# grids_v02.net
KiCad netlist of a schematic drawn in EAGLE
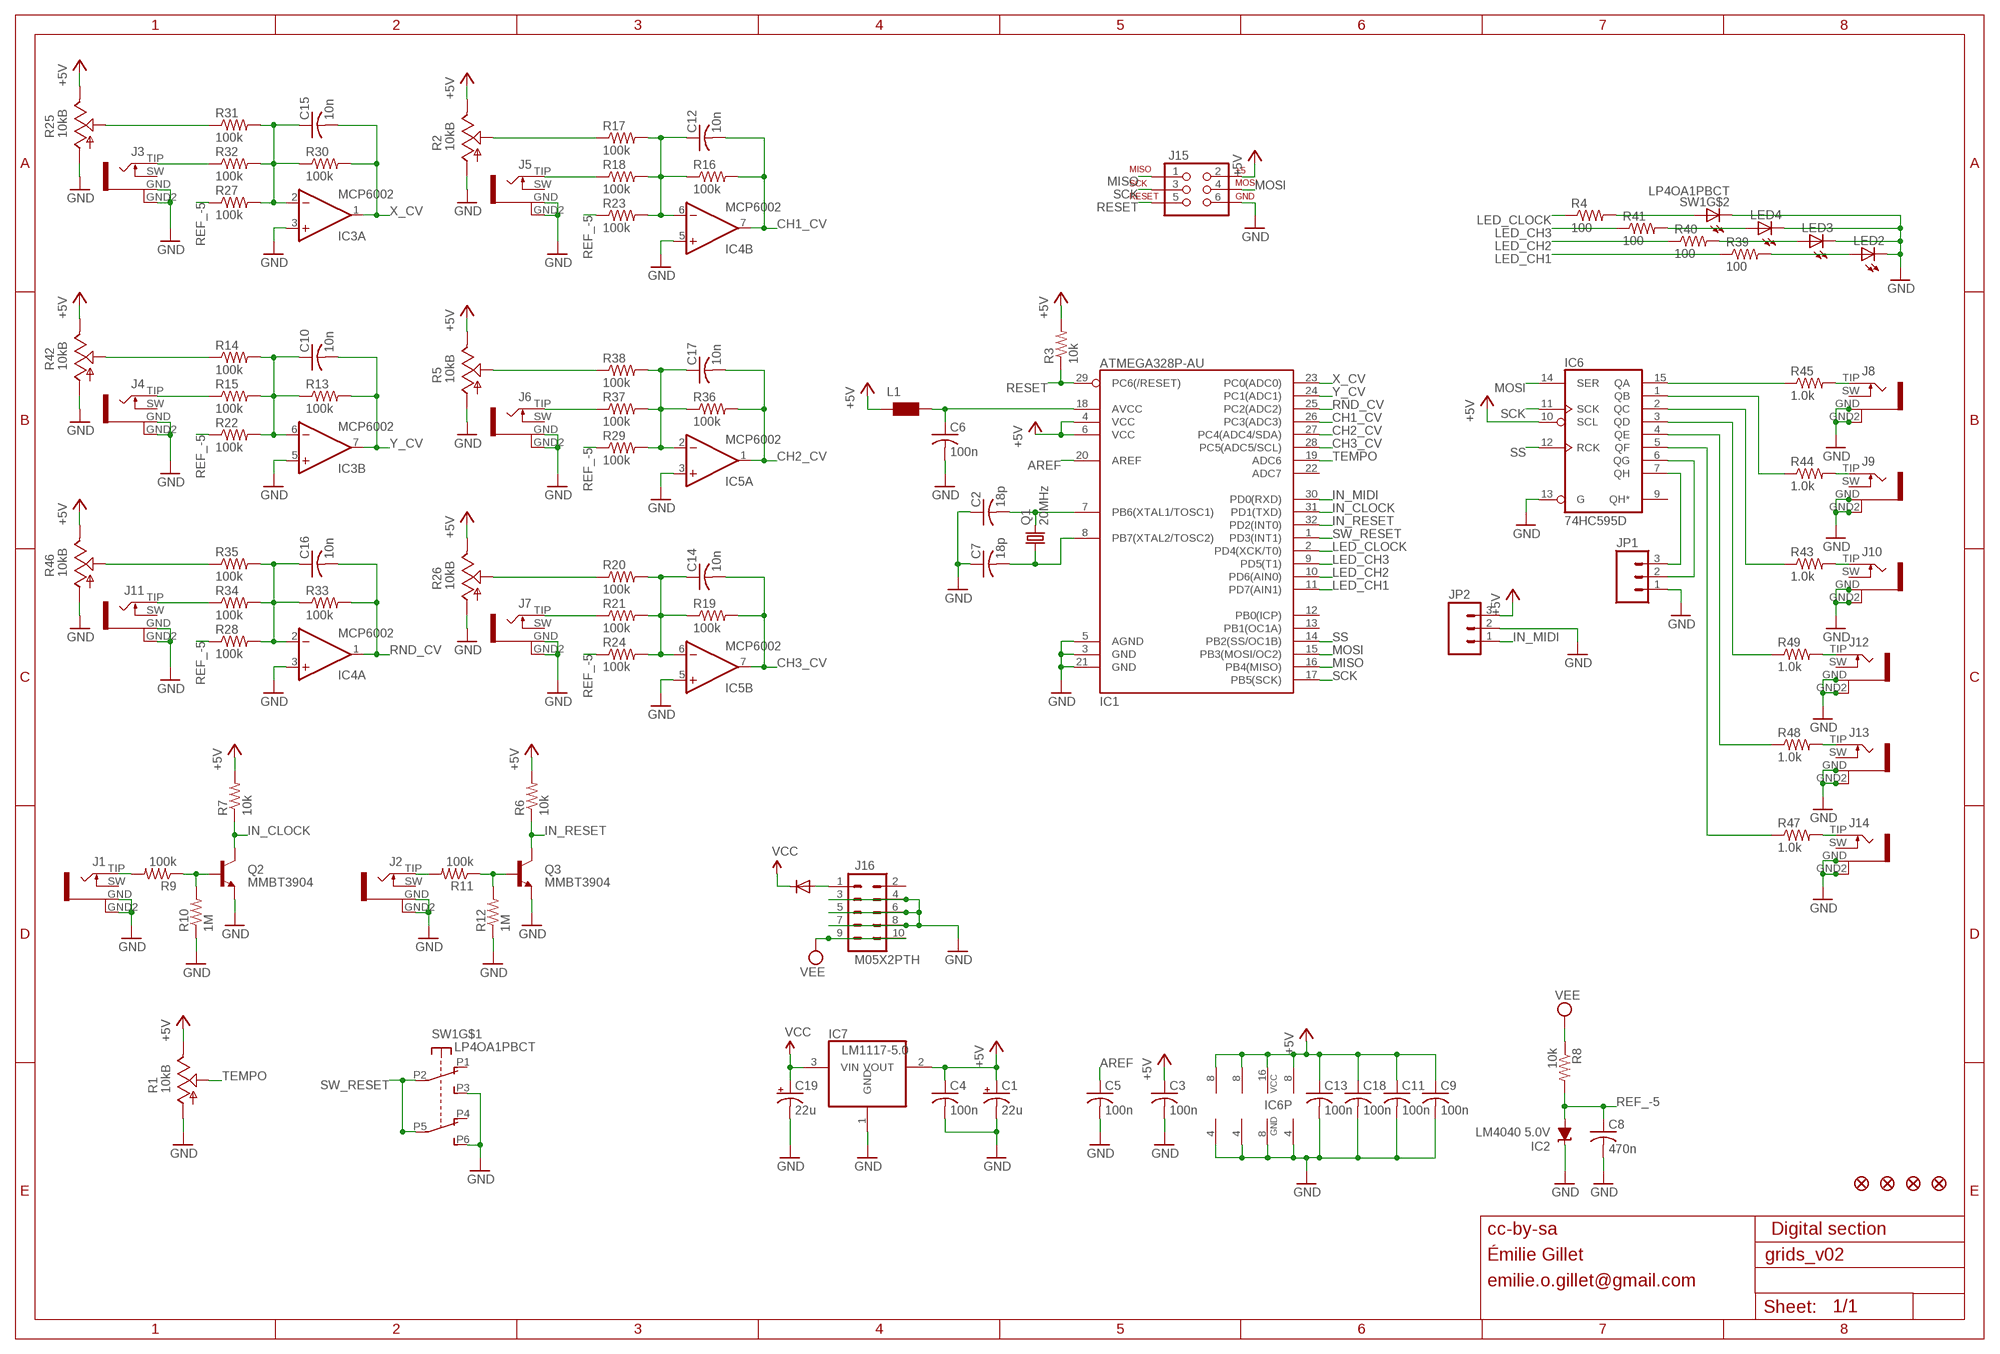
[diagram p0: schematic, sheet 1]

(export (version "E")
  (design (tool "Eeschema 10.0.6"))
  (components
    (comp (ref "C1")
      (value "22u")
      (footprint "eagle-import:PANASONIC_C")
      (libsource (lib "eagle-import") (part "CPOL-USC"))
    )
    (comp (ref "C2")
      (value "18p")
      (footprint "eagle-import:C0603")
      (libsource (lib "eagle-import") (part "C-USC0603"))
    )
    (comp (ref "C3")
      (value "100n")
      (footprint "eagle-import:C0603")
      (libsource (lib "eagle-import") (part "C-USC0603"))
    )
    (comp (ref "C4")
      (value "100n")
      (footprint "eagle-import:C0603")
      (libsource (lib "eagle-import") (part "C-USC0603"))
    )
    (comp (ref "C5")
      (value "100n")
      (footprint "eagle-import:C0603")
      (libsource (lib "eagle-import") (part "C-USC0603"))
    )
    (comp (ref "C6")
      (value "100n")
      (footprint "eagle-import:C0603")
      (libsource (lib "eagle-import") (part "C-USC0603"))
    )
    (comp (ref "C7")
      (value "18p")
      (footprint "eagle-import:C0603")
      (libsource (lib "eagle-import") (part "C-USC0603"))
    )
    (comp (ref "C8")
      (value "470n")
      (footprint "eagle-import:C0603")
      (libsource (lib "eagle-import") (part "C-USC0603"))
    )
    (comp (ref "C9")
      (value "100n")
      (footprint "eagle-import:C0603")
      (libsource (lib "eagle-import") (part "C-USC0603"))
    )
    (comp (ref "C10")
      (value "10n")
      (footprint "eagle-import:C0603")
      (libsource (lib "eagle-import") (part "C-USC0603"))
    )
    (comp (ref "C11")
      (value "100n")
      (footprint "eagle-import:C0603")
      (libsource (lib "eagle-import") (part "C-USC0603"))
    )
    (comp (ref "C12")
      (value "10n")
      (footprint "eagle-import:C0603")
      (libsource (lib "eagle-import") (part "C-USC0603"))
    )
    (comp (ref "C13")
      (value "100n")
      (footprint "eagle-import:C0603")
      (libsource (lib "eagle-import") (part "C-USC0603"))
    )
    (comp (ref "C14")
      (value "10n")
      (footprint "eagle-import:C0603")
      (libsource (lib "eagle-import") (part "C-USC0603"))
    )
    (comp (ref "C15")
      (value "10n")
      (footprint "eagle-import:C0603")
      (libsource (lib "eagle-import") (part "C-USC0603"))
    )
    (comp (ref "C16")
      (value "10n")
      (footprint "eagle-import:C0603")
      (libsource (lib "eagle-import") (part "C-USC0603"))
    )
    (comp (ref "C17")
      (value "10n")
      (footprint "eagle-import:C0603")
      (libsource (lib "eagle-import") (part "C-USC0603"))
    )
    (comp (ref "C18")
      (value "100n")
      (footprint "eagle-import:C0603")
      (libsource (lib "eagle-import") (part "C-USC0603"))
    )
    (comp (ref "C19")
      (value "22u")
      (footprint "eagle-import:PANASONIC_C")
      (libsource (lib "eagle-import") (part "CPOL-USC"))
    )
    (comp (ref "D1")
      (value "1N5819HW")
      (footprint "eagle-import:SOD123")
      (libsource (lib "eagle-import") (part "DIODE-SOD123"))
    )
    (comp (ref "F1")
      (value "FIDUCIAL1X2")
      (footprint "eagle-import:FIDUCIAL-1X2")
      (libsource (lib "eagle-import") (part "FIDUCIAL1X2"))
    )
    (comp (ref "F2")
      (value "FIDUCIAL1X2")
      (footprint "eagle-import:FIDUCIAL-1X2")
      (libsource (lib "eagle-import") (part "FIDUCIAL1X2"))
    )
    (comp (ref "F3")
      (value "FIDUCIAL1X2")
      (footprint "eagle-import:FIDUCIAL-1X2")
      (libsource (lib "eagle-import") (part "FIDUCIAL1X2"))
    )
    (comp (ref "F4")
      (value "FIDUCIAL1X2")
      (footprint "eagle-import:FIDUCIAL-1X2")
      (libsource (lib "eagle-import") (part "FIDUCIAL1X2"))
    )
    (comp (ref "IC1")
      (value "ATMEGA328P-AU")
      (footprint "eagle-import:TQFP32-08")
      (libsource (lib "eagle-import") (part "ATMEGA168"))
    )
    (comp (ref "IC2")
      (value "LM4040 5.0V")
      (footprint "eagle-import:DBZ_R-PDSO-G3")
      (libsource (lib "eagle-import") (part "LM4041DBZC12"))
    )
    (comp (ref "IC3")
      (value "MCP6002")
      (footprint "eagle-import:SO08")
      (libsource (lib "eagle-import") (part "TL072D"))
    )
    (comp (ref "IC4")
      (value "MCP6002")
      (footprint "eagle-import:SO08")
      (libsource (lib "eagle-import") (part "TL072D"))
    )
    (comp (ref "IC5")
      (value "MCP6002")
      (footprint "eagle-import:SO08")
      (libsource (lib "eagle-import") (part "TL072D"))
    )
    (comp (ref "IC6")
      (value "74HC595D")
      (footprint "eagle-import:SO16")
      (libsource (lib "eagle-import") (part "74595DHC"))
    )
    (comp (ref "IC7")
      (value "LM1117-5.0")
      (footprint "eagle-import:SOT223")
      (libsource (lib "eagle-import") (part "REG1117"))
    )
    (comp (ref "J1")
      (value "PJ301WQP")
      (footprint "eagle-import:WQP_PJ_301BM")
      (libsource (lib "eagle-import") (part "PJ301WQP"))
    )
    (comp (ref "J2")
      (value "PJ301WQP")
      (footprint "eagle-import:WQP_PJ_301BM")
      (libsource (lib "eagle-import") (part "PJ301WQP"))
    )
    (comp (ref "J3")
      (value "PJ301WQP")
      (footprint "eagle-import:WQP_PJ_301BM")
      (libsource (lib "eagle-import") (part "PJ301WQP"))
    )
    (comp (ref "J4")
      (value "PJ301WQP")
      (footprint "eagle-import:WQP_PJ_301BM")
      (libsource (lib "eagle-import") (part "PJ301WQP"))
    )
    (comp (ref "J5")
      (value "PJ301WQP")
      (footprint "eagle-import:WQP_PJ_301BM")
      (libsource (lib "eagle-import") (part "PJ301WQP"))
    )
    (comp (ref "J6")
      (value "PJ301WQP")
      (footprint "eagle-import:WQP_PJ_301BM")
      (libsource (lib "eagle-import") (part "PJ301WQP"))
    )
    (comp (ref "J7")
      (value "PJ301WQP")
      (footprint "eagle-import:WQP_PJ_301BM")
      (libsource (lib "eagle-import") (part "PJ301WQP"))
    )
    (comp (ref "J8")
      (value "PJ301WQP")
      (footprint "eagle-import:WQP_PJ_301BM")
      (libsource (lib "eagle-import") (part "PJ301WQP"))
    )
    (comp (ref "J9")
      (value "PJ301WQP")
      (footprint "eagle-import:WQP_PJ_301BM")
      (libsource (lib "eagle-import") (part "PJ301WQP"))
    )
    (comp (ref "J10")
      (value "PJ301WQP")
      (footprint "eagle-import:WQP_PJ_301BM")
      (libsource (lib "eagle-import") (part "PJ301WQP"))
    )
    (comp (ref "J11")
      (value "PJ301WQP")
      (footprint "eagle-import:WQP_PJ_301BM")
      (libsource (lib "eagle-import") (part "PJ301WQP"))
    )
    (comp (ref "J12")
      (value "PJ301WQP")
      (footprint "eagle-import:WQP_PJ_301BM")
      (libsource (lib "eagle-import") (part "PJ301WQP"))
    )
    (comp (ref "J13")
      (value "PJ301WQP")
      (footprint "eagle-import:WQP_PJ_301BM")
      (libsource (lib "eagle-import") (part "PJ301WQP"))
    )
    (comp (ref "J14")
      (value "PJ301WQP")
      (footprint "eagle-import:WQP_PJ_301BM")
      (libsource (lib "eagle-import") (part "PJ301WQP"))
    )
    (comp (ref "J15")
      (value "AVR_SPI_PRG_6PTH")
      (footprint "eagle-import:2X3")
      (libsource (lib "eagle-import") (part "AVR_SPI_PRG_6PTH"))
    )
    (comp (ref "J16")
      (value "M05X2PTH")
      (footprint "eagle-import:AVR_ICSP")
      (libsource (lib "eagle-import") (part "M05X2PTH"))
    )
    (comp (ref "JP1")
      (value "M03PTH")
      (footprint "eagle-import:1X03")
      (libsource (lib "eagle-import") (part "M03PTH"))
    )
    (comp (ref "JP2")
      (value "M03PTH")
      (footprint "eagle-import:1X03")
      (libsource (lib "eagle-import") (part "M03PTH"))
    )
    (comp (ref "L1")
      (value "WE-CBF_0603")
      (footprint "eagle-import:0603")
      (libsource (lib "eagle-import") (part "WE-CBF_0603"))
    )
    (comp (ref "LED2")
      (value "LED3MM")
      (footprint "eagle-import:LED3MM")
      (libsource (lib "eagle-import") (part "LED3MM"))
    )
    (comp (ref "LED3")
      (value "LED3MM")
      (footprint "eagle-import:LED3MM")
      (libsource (lib "eagle-import") (part "LED3MM"))
    )
    (comp (ref "LED4")
      (value "LED3MM")
      (footprint "eagle-import:LED3MM")
      (libsource (lib "eagle-import") (part "LED3MM"))
    )
    (comp (ref "Q1")
      (value "20MHz")
      (footprint "eagle-import:HC49UP")
      (libsource (lib "eagle-import") (part "CRYSTALHC49UP"))
    )
    (comp (ref "Q2")
      (value "MMBT3904")
      (footprint "eagle-import:SOT23-BEC")
      (libsource (lib "eagle-import") (part "-NPN-SOT23-BECMMBT3904LT1"))
    )
    (comp (ref "Q3")
      (value "MMBT3904")
      (footprint "eagle-import:SOT23-BEC")
      (libsource (lib "eagle-import") (part "-NPN-SOT23-BECMMBT3904LT1"))
    )
    (comp (ref "R1")
      (value "10kB")
      (footprint "eagle-import:ALPS_POT_VERTICAL_PS")
      (libsource (lib "eagle-import") (part "POT_USVERTICAL_PS"))
    )
    (comp (ref "R2")
      (value "10kB")
      (footprint "eagle-import:ALPS_POT_VERTICAL_PS")
      (libsource (lib "eagle-import") (part "POT_USVERTICAL_PS"))
    )
    (comp (ref "R3")
      (value "10k")
      (footprint "eagle-import:R0603")
      (libsource (lib "eagle-import") (part "R-US_R0603"))
    )
    (comp (ref "R4")
      (value "100")
      (footprint "eagle-import:R0603")
      (libsource (lib "eagle-import") (part "R-US_R0603"))
    )
    (comp (ref "R5")
      (value "10kB")
      (footprint "eagle-import:ALPS_POT_VERTICAL_PS")
      (libsource (lib "eagle-import") (part "POT_USVERTICAL_PS"))
    )
    (comp (ref "R6")
      (value "10k")
      (footprint "eagle-import:R0603")
      (libsource (lib "eagle-import") (part "R-US_R0603"))
    )
    (comp (ref "R7")
      (value "10k")
      (footprint "eagle-import:R0603")
      (libsource (lib "eagle-import") (part "R-US_R0603"))
    )
    (comp (ref "R8")
      (value "10k")
      (footprint "eagle-import:R0603")
      (libsource (lib "eagle-import") (part "resistor_R-US_R0603"))
    )
    (comp (ref "R9")
      (value "100k")
      (footprint "eagle-import:R0603")
      (libsource (lib "eagle-import") (part "R-US_R0603"))
    )
    (comp (ref "R10")
      (value "1M")
      (footprint "eagle-import:R0603")
      (libsource (lib "eagle-import") (part "R-US_R0603"))
    )
    (comp (ref "R11")
      (value "100k")
      (footprint "eagle-import:R0603")
      (libsource (lib "eagle-import") (part "R-US_R0603"))
    )
    (comp (ref "R12")
      (value "1M")
      (footprint "eagle-import:R0603")
      (libsource (lib "eagle-import") (part "R-US_R0603"))
    )
    (comp (ref "R13")
      (value "100k")
      (footprint "eagle-import:R0603")
      (libsource (lib "eagle-import") (part "R-US_R0603"))
    )
    (comp (ref "R14")
      (value "100k")
      (footprint "eagle-import:R0603")
      (libsource (lib "eagle-import") (part "R-US_R0603"))
    )
    (comp (ref "R15")
      (value "100k")
      (footprint "eagle-import:R0603")
      (libsource (lib "eagle-import") (part "R-US_R0603"))
    )
    (comp (ref "R16")
      (value "100k")
      (footprint "eagle-import:R0603")
      (libsource (lib "eagle-import") (part "R-US_R0603"))
    )
    (comp (ref "R17")
      (value "100k")
      (footprint "eagle-import:R0603")
      (libsource (lib "eagle-import") (part "R-US_R0603"))
    )
    (comp (ref "R18")
      (value "100k")
      (footprint "eagle-import:R0603")
      (libsource (lib "eagle-import") (part "R-US_R0603"))
    )
    (comp (ref "R19")
      (value "100k")
      (footprint "eagle-import:R0603")
      (libsource (lib "eagle-import") (part "R-US_R0603"))
    )
    (comp (ref "R20")
      (value "100k")
      (footprint "eagle-import:R0603")
      (libsource (lib "eagle-import") (part "R-US_R0603"))
    )
    (comp (ref "R21")
      (value "100k")
      (footprint "eagle-import:R0603")
      (libsource (lib "eagle-import") (part "R-US_R0603"))
    )
    (comp (ref "R22")
      (value "100k")
      (footprint "eagle-import:R0603")
      (libsource (lib "eagle-import") (part "R-US_R0603"))
    )
    (comp (ref "R23")
      (value "100k")
      (footprint "eagle-import:R0603")
      (libsource (lib "eagle-import") (part "R-US_R0603"))
    )
    (comp (ref "R24")
      (value "100k")
      (footprint "eagle-import:R0603")
      (libsource (lib "eagle-import") (part "R-US_R0603"))
    )
    (comp (ref "R25")
      (value "10kB")
      (footprint "eagle-import:ALPS_POT_VERTICAL_PS")
      (libsource (lib "eagle-import") (part "POT_USVERTICAL_PS"))
    )
    (comp (ref "R26")
      (value "10kB")
      (footprint "eagle-import:ALPS_POT_VERTICAL_PS")
      (libsource (lib "eagle-import") (part "POT_USVERTICAL_PS"))
    )
    (comp (ref "R27")
      (value "100k")
      (footprint "eagle-import:R0603")
      (libsource (lib "eagle-import") (part "R-US_R0603"))
    )
    (comp (ref "R28")
      (value "100k")
      (footprint "eagle-import:R0603")
      (libsource (lib "eagle-import") (part "R-US_R0603"))
    )
    (comp (ref "R29")
      (value "100k")
      (footprint "eagle-import:R0603")
      (libsource (lib "eagle-import") (part "R-US_R0603"))
    )
    (comp (ref "R30")
      (value "100k")
      (footprint "eagle-import:R0603")
      (libsource (lib "eagle-import") (part "R-US_R0603"))
    )
    (comp (ref "R31")
      (value "100k")
      (footprint "eagle-import:R0603")
      (libsource (lib "eagle-import") (part "R-US_R0603"))
    )
    (comp (ref "R32")
      (value "100k")
      (footprint "eagle-import:R0603")
      (libsource (lib "eagle-import") (part "R-US_R0603"))
    )
    (comp (ref "R33")
      (value "100k")
      (footprint "eagle-import:R0603")
      (libsource (lib "eagle-import") (part "R-US_R0603"))
    )
    (comp (ref "R34")
      (value "100k")
      (footprint "eagle-import:R0603")
      (libsource (lib "eagle-import") (part "R-US_R0603"))
    )
    (comp (ref "R35")
      (value "100k")
      (footprint "eagle-import:R0603")
      (libsource (lib "eagle-import") (part "R-US_R0603"))
    )
    (comp (ref "R36")
      (value "100k")
      (footprint "eagle-import:R0603")
      (libsource (lib "eagle-import") (part "R-US_R0603"))
    )
    (comp (ref "R37")
      (value "100k")
      (footprint "eagle-import:R0603")
      (libsource (lib "eagle-import") (part "R-US_R0603"))
    )
    (comp (ref "R38")
      (value "100k")
      (footprint "eagle-import:R0603")
      (libsource (lib "eagle-import") (part "R-US_R0603"))
    )
    (comp (ref "R39")
      (value "100")
      (footprint "eagle-import:R0603")
      (libsource (lib "eagle-import") (part "R-US_R0603"))
    )
    (comp (ref "R40")
      (value "100")
      (footprint "eagle-import:R0603")
      (libsource (lib "eagle-import") (part "R-US_R0603"))
    )
    (comp (ref "R41")
      (value "100")
      (footprint "eagle-import:R0603")
      (libsource (lib "eagle-import") (part "R-US_R0603"))
    )
    (comp (ref "R42")
      (value "10kB")
      (footprint "eagle-import:ALPS_POT_VERTICAL_PS4")
      (libsource (lib "eagle-import") (part "POT_USVERTICAL_PS4"))
    )
    (comp (ref "R43")
      (value "1.0k")
      (footprint "eagle-import:R0603")
      (libsource (lib "eagle-import") (part "R-US_R0603"))
    )
    (comp (ref "R44")
      (value "1.0k")
      (footprint "eagle-import:R0603")
      (libsource (lib "eagle-import") (part "R-US_R0603"))
    )
    (comp (ref "R45")
      (value "1.0k")
      (footprint "eagle-import:R0603")
      (libsource (lib "eagle-import") (part "R-US_R0603"))
    )
    (comp (ref "R46")
      (value "10kB")
      (footprint "eagle-import:ALPS_POT_VERTICAL_PS")
      (libsource (lib "eagle-import") (part "POT_USVERTICAL_PS"))
    )
    (comp (ref "R47")
      (value "1.0k")
      (footprint "eagle-import:R0603")
      (libsource (lib "eagle-import") (part "R-US_R0603"))
    )
    (comp (ref "R48")
      (value "1.0k")
      (footprint "eagle-import:R0603")
      (libsource (lib "eagle-import") (part "R-US_R0603"))
    )
    (comp (ref "R49")
      (value "1.0k")
      (footprint "eagle-import:R0603")
      (libsource (lib "eagle-import") (part "R-US_R0603"))
    )
    (comp (ref "SW1")
      (value "LP4OA1PBCT")
      (footprint "eagle-import:LP4OA1PBCT")
      (libsource (lib "eagle-import") (part "LP4OA1PBCT"))
    )
  )
  (nets
    (net (code "1") (name "+5V") (class "Default")
      (node (ref "C1") (pin "+") (pinfunction "+_+") (pintype "passive"))
      (node (ref "C11") (pin "1") (pinfunction "1_1") (pintype "passive"))
      (node (ref "C13") (pin "1") (pinfunction "1_1") (pintype "passive"))
      (node (ref "C18") (pin "1") (pinfunction "1_1") (pintype "passive"))
      (node (ref "C3") (pin "1") (pinfunction "1_1") (pintype "passive"))
      (node (ref "C4") (pin "1") (pinfunction "1_1") (pintype "passive"))
      (node (ref "C9") (pin "1") (pinfunction "1_1") (pintype "passive"))
      (node (ref "IC1") (pin "4") (pinfunction "VCC_4") (pintype "bidirectional"))
      (node (ref "IC1") (pin "6") (pinfunction "VCC_6") (pintype "bidirectional"))
      (node (ref "IC3") (pin "8") (pinfunction "V+_8") (pintype "power_in"))
      (node (ref "IC4") (pin "8") (pinfunction "V+_8") (pintype "power_in"))
      (node (ref "IC5") (pin "8") (pinfunction "V+_8") (pintype "power_in"))
      (node (ref "IC6") (pin "10") (pinfunction "SCL_10") (pintype "input"))
      (node (ref "IC6") (pin "16") (pinfunction "VCC_16") (pintype "power_in"))
      (node (ref "IC7") (pin "2") (pinfunction "VOUT_2") (pintype "output"))
      (node (ref "J15") (pin "2") (pinfunction "2_2") (pintype "passive"))
      (node (ref "JP2") (pin "3") (pinfunction "3_3") (pintype "passive"))
      (node (ref "L1") (pin "1") (pinfunction "1_1") (pintype "passive"))
      (node (ref "R1") (pin "P$1") (pinfunction "E_P$1") (pintype "passive"))
      (node (ref "R2") (pin "P$1") (pinfunction "E_P$1") (pintype "passive"))
      (node (ref "R25") (pin "P$1") (pinfunction "E_P$1") (pintype "passive"))
      (node (ref "R26") (pin "P$1") (pinfunction "E_P$1") (pintype "passive"))
      (node (ref "R3") (pin "2") (pinfunction "2_2") (pintype "passive"))
      (node (ref "R42") (pin "P$1") (pinfunction "E_P$1") (pintype "passive"))
      (node (ref "R46") (pin "P$1") (pinfunction "E_P$1") (pintype "passive"))
      (node (ref "R5") (pin "P$1") (pinfunction "E_P$1") (pintype "passive"))
      (node (ref "R6") (pin "2") (pinfunction "2_2") (pintype "passive"))
      (node (ref "R7") (pin "2") (pinfunction "2_2") (pintype "passive"))
    )
    (net (code "2") (name "/AREF") (class "Default")
      (node (ref "C5") (pin "1") (pinfunction "1_1") (pintype "passive"))
      (node (ref "IC1") (pin "20") (pinfunction "AREF_20") (pintype "bidirectional"))
    )
    (net (code "3") (name "/CH1_CV") (class "Default")
      (node (ref "C12") (pin "2") (pinfunction "2_2") (pintype "passive"))
      (node (ref "IC1") (pin "26") (pinfunction "PC3(ADC3)_26") (pintype "bidirectional"))
      (node (ref "IC4") (pin "7") (pinfunction "OUT_7") (pintype "output"))
      (node (ref "R16") (pin "2") (pinfunction "2_2") (pintype "passive"))
    )
    (net (code "4") (name "/CH2_CV") (class "Default")
      (node (ref "C17") (pin "2") (pinfunction "2_2") (pintype "passive"))
      (node (ref "IC1") (pin "27") (pinfunction "PC4(ADC4/SDA)_27") (pintype "bidirectional"))
      (node (ref "IC5") (pin "1") (pinfunction "OUT_1") (pintype "output"))
      (node (ref "R36") (pin "2") (pinfunction "2_2") (pintype "passive"))
    )
    (net (code "5") (name "/CH3_CV") (class "Default")
      (node (ref "C14") (pin "2") (pinfunction "2_2") (pintype "passive"))
      (node (ref "IC1") (pin "28") (pinfunction "PC5(ADC5/SCL)_28") (pintype "bidirectional"))
      (node (ref "IC5") (pin "7") (pinfunction "OUT_7") (pintype "output"))
      (node (ref "R19") (pin "2") (pinfunction "2_2") (pintype "passive"))
    )
    (net (code "6") (name "/IN_CLOCK") (class "Default")
      (node (ref "IC1") (pin "31") (pinfunction "PD1(TXD)_31") (pintype "bidirectional"))
      (node (ref "Q2") (pin "C") (pinfunction "C_C") (pintype "passive"))
      (node (ref "R7") (pin "1") (pinfunction "1_1") (pintype "passive"))
    )
    (net (code "7") (name "/IN_MIDI") (class "Default")
      (node (ref "IC1") (pin "30") (pinfunction "PD0(RXD)_30") (pintype "bidirectional"))
      (node (ref "JP2") (pin "1") (pinfunction "1_1") (pintype "passive"))
    )
    (net (code "8") (name "/IN_RESET") (class "Default")
      (node (ref "IC1") (pin "32") (pinfunction "PD2(INT0)_32") (pintype "bidirectional"))
      (node (ref "Q3") (pin "C") (pinfunction "C_C") (pintype "passive"))
      (node (ref "R6") (pin "1") (pinfunction "1_1") (pintype "passive"))
    )
    (net (code "9") (name "/LED_CH1") (class "Default")
      (node (ref "IC1") (pin "11") (pinfunction "PD7(AIN1)_11") (pintype "bidirectional"))
      (node (ref "R39") (pin "1") (pinfunction "1_1") (pintype "passive"))
    )
    (net (code "10") (name "/LED_CH2") (class "Default")
      (node (ref "IC1") (pin "10") (pinfunction "PD6(AIN0)_10") (pintype "bidirectional"))
      (node (ref "R40") (pin "1") (pinfunction "1_1") (pintype "passive"))
    )
    (net (code "11") (name "/LED_CH3") (class "Default")
      (node (ref "IC1") (pin "9") (pinfunction "PD5(T1)_9") (pintype "bidirectional"))
      (node (ref "R41") (pin "1") (pinfunction "1_1") (pintype "passive"))
    )
    (net (code "12") (name "/LED_CLOCK") (class "Default")
      (node (ref "IC1") (pin "2") (pinfunction "PD4(XCK/T0)_2") (pintype "bidirectional"))
      (node (ref "R4") (pin "1") (pinfunction "1_1") (pintype "passive"))
    )
    (net (code "13") (name "/MISO") (class "Default")
      (node (ref "IC1") (pin "16") (pinfunction "PB4(MISO)_16") (pintype "bidirectional"))
      (node (ref "J15") (pin "1") (pinfunction "1_1") (pintype "passive"))
    )
    (net (code "14") (name "/MOSI") (class "Default")
      (node (ref "IC1") (pin "15") (pinfunction "PB3(MOSI/OC2)_15") (pintype "bidirectional"))
      (node (ref "IC6") (pin "14") (pinfunction "SER_14") (pintype "input"))
      (node (ref "J15") (pin "4") (pinfunction "4_4") (pintype "passive"))
    )
    (net (code "15") (name "/REF_-5") (class "Default")
      (node (ref "C8") (pin "1") (pinfunction "1_1") (pintype "passive"))
      (node (ref "IC2") (pin "2") (pinfunction "A_2") (pintype "passive"))
      (node (ref "R22") (pin "1") (pinfunction "1_1") (pintype "passive"))
      (node (ref "R23") (pin "1") (pinfunction "1_1") (pintype "passive"))
      (node (ref "R24") (pin "1") (pinfunction "1_1") (pintype "passive"))
      (node (ref "R27") (pin "1") (pinfunction "1_1") (pintype "passive"))
      (node (ref "R28") (pin "1") (pinfunction "1_1") (pintype "passive"))
      (node (ref "R29") (pin "1") (pinfunction "1_1") (pintype "passive"))
      (node (ref "R8") (pin "2") (pinfunction "2_2") (pintype "passive"))
    )
    (net (code "16") (name "/RESET") (class "Default")
      (node (ref "IC1") (pin "29") (pinfunction "PC6(/RESET)_29") (pintype "bidirectional"))
      (node (ref "J15") (pin "5") (pinfunction "5_5") (pintype "passive"))
      (node (ref "R3") (pin "1") (pinfunction "1_1") (pintype "passive"))
    )
    (net (code "17") (name "/RND_CV") (class "Default")
      (node (ref "C16") (pin "2") (pinfunction "2_2") (pintype "passive"))
      (node (ref "IC1") (pin "25") (pinfunction "PC2(ADC2)_25") (pintype "bidirectional"))
      (node (ref "IC4") (pin "1") (pinfunction "OUT_1") (pintype "output"))
      (node (ref "R33") (pin "2") (pinfunction "2_2") (pintype "passive"))
    )
    (net (code "18") (name "/SCK") (class "Default")
      (node (ref "IC1") (pin "17") (pinfunction "PB5(SCK)_17") (pintype "bidirectional"))
      (node (ref "IC6") (pin "11") (pinfunction "SCK_11") (pintype "input"))
      (node (ref "J15") (pin "3") (pinfunction "3_3") (pintype "passive"))
    )
    (net (code "19") (name "/SS") (class "Default")
      (node (ref "IC1") (pin "14") (pinfunction "PB2(SS/OC1B)_14") (pintype "bidirectional"))
      (node (ref "IC6") (pin "12") (pinfunction "RCK_12") (pintype "input"))
    )
    (net (code "20") (name "/SW_RESET") (class "Default")
      (node (ref "IC1") (pin "1") (pinfunction "PD3(INT1)_1") (pintype "bidirectional"))
      (node (ref "SW1") (pin "P2") (pinfunction "A2_P2") (pintype "passive"))
      (node (ref "SW1") (pin "P5") (pinfunction "B2_P5") (pintype "passive"))
    )
    (net (code "21") (name "/TEMPO") (class "Default")
      (node (ref "IC1") (pin "19") (pinfunction "ADC6_19") (pintype "bidirectional"))
      (node (ref "R1") (pin "P$2") (pinfunction "S_P$2") (pintype "passive"))
    )
    (net (code "22") (name "/X_CV") (class "Default")
      (node (ref "C15") (pin "2") (pinfunction "2_2") (pintype "passive"))
      (node (ref "IC1") (pin "23") (pinfunction "PC0(ADC0)_23") (pintype "bidirectional"))
      (node (ref "IC3") (pin "1") (pinfunction "OUT_1") (pintype "output"))
      (node (ref "R30") (pin "2") (pinfunction "2_2") (pintype "passive"))
    )
    (net (code "23") (name "/Y_CV") (class "Default")
      (node (ref "C10") (pin "2") (pinfunction "2_2") (pintype "passive"))
      (node (ref "IC1") (pin "24") (pinfunction "PC1(ADC1)_24") (pintype "bidirectional"))
      (node (ref "IC3") (pin "7") (pinfunction "OUT_7") (pintype "output"))
      (node (ref "R13") (pin "2") (pinfunction "2_2") (pintype "passive"))
    )
    (net (code "24") (name "GND") (class "Default")
      (node (ref "C1") (pin "-") (pinfunction "-_-") (pintype "passive"))
      (node (ref "C11") (pin "2") (pinfunction "2_2") (pintype "passive"))
      (node (ref "C13") (pin "2") (pinfunction "2_2") (pintype "passive"))
      (node (ref "C18") (pin "2") (pinfunction "2_2") (pintype "passive"))
      (node (ref "C19") (pin "-") (pinfunction "-_-") (pintype "passive"))
      (node (ref "C2") (pin "1") (pinfunction "1_1") (pintype "passive"))
      (node (ref "C3") (pin "2") (pinfunction "2_2") (pintype "passive"))
      (node (ref "C4") (pin "2") (pinfunction "2_2") (pintype "passive"))
      (node (ref "C5") (pin "2") (pinfunction "2_2") (pintype "passive"))
      (node (ref "C6") (pin "2") (pinfunction "2_2") (pintype "passive"))
      (node (ref "C7") (pin "1") (pinfunction "1_1") (pintype "passive"))
      (node (ref "C8") (pin "2") (pinfunction "2_2") (pintype "passive"))
      (node (ref "C9") (pin "2") (pinfunction "2_2") (pintype "passive"))
      (node (ref "IC1") (pin "21") (pinfunction "GND_21") (pintype "bidirectional"))
      (node (ref "IC1") (pin "3") (pinfunction "GND_3") (pintype "bidirectional"))
      (node (ref "IC1") (pin "5") (pinfunction "AGND_5") (pintype "bidirectional"))
      (node (ref "IC2") (pin "1") (pinfunction "C_1") (pintype "passive"))
      (node (ref "IC3") (pin "3") (pinfunction "+IN_3") (pintype "input"))
      (node (ref "IC3") (pin "4") (pinfunction "V-_4") (pintype "power_in"))
      (node (ref "IC3") (pin "5") (pinfunction "+IN_5") (pintype "input"))
      (node (ref "IC4") (pin "3") (pinfunction "+IN_3") (pintype "input"))
      (node (ref "IC4") (pin "4") (pinfunction "V-_4") (pintype "power_in"))
      (node (ref "IC4") (pin "5") (pinfunction "+IN_5") (pintype "input"))
      (node (ref "IC5") (pin "3") (pinfunction "+IN_3") (pintype "input"))
      (node (ref "IC5") (pin "4") (pinfunction "V-_4") (pintype "power_in"))
      (node (ref "IC5") (pin "5") (pinfunction "+IN_5") (pintype "input"))
      (node (ref "IC6") (pin "13") (pinfunction "G_13") (pintype "input"))
      (node (ref "IC6") (pin "8") (pinfunction "GND_8") (pintype "power_in"))
      (node (ref "IC7") (pin "1") (pinfunction "GND_1") (pintype "power_in"))
      (node (ref "J1") (pin "GND") (pinfunction "1_GND") (pintype "passive"))
      (node (ref "J1") (pin "GND2") (pinfunction "4_GND2") (pintype "passive"))
      (node (ref "J10") (pin "GND") (pinfunction "1_GND") (pintype "passive"))
      (node (ref "J10") (pin "GND2") (pinfunction "4_GND2") (pintype "passive"))
      (node (ref "J11") (pin "GND") (pinfunction "1_GND") (pintype "passive"))
      (node (ref "J11") (pin "GND2") (pinfunction "4_GND2") (pintype "passive"))
      (node (ref "J12") (pin "GND") (pinfunction "1_GND") (pintype "passive"))
      (node (ref "J12") (pin "GND2") (pinfunction "4_GND2") (pintype "passive"))
      (node (ref "J13") (pin "GND") (pinfunction "1_GND") (pintype "passive"))
      (node (ref "J13") (pin "GND2") (pinfunction "4_GND2") (pintype "passive"))
      (node (ref "J14") (pin "GND") (pinfunction "1_GND") (pintype "passive"))
      (node (ref "J14") (pin "GND2") (pinfunction "4_GND2") (pintype "passive"))
      (node (ref "J15") (pin "6") (pinfunction "6_6") (pintype "passive"))
      (node (ref "J16") (pin "3") (pinfunction "3_3") (pintype "passive"))
      (node (ref "J16") (pin "4") (pinfunction "4_4") (pintype "passive"))
      (node (ref "J16") (pin "5") (pinfunction "5_5") (pintype "passive"))
      (node (ref "J16") (pin "6") (pinfunction "6_6") (pintype "passive"))
      (node (ref "J16") (pin "7") (pinfunction "7_7") (pintype "passive"))
      (node (ref "J16") (pin "8") (pinfunction "8_8") (pintype "passive"))
      (node (ref "J2") (pin "GND") (pinfunction "1_GND") (pintype "passive"))
      (node (ref "J2") (pin "GND2") (pinfunction "4_GND2") (pintype "passive"))
      (node (ref "J3") (pin "GND") (pinfunction "1_GND") (pintype "passive"))
      (node (ref "J3") (pin "GND2") (pinfunction "4_GND2") (pintype "passive"))
      (node (ref "J4") (pin "GND") (pinfunction "1_GND") (pintype "passive"))
      (node (ref "J4") (pin "GND2") (pinfunction "4_GND2") (pintype "passive"))
      (node (ref "J5") (pin "GND") (pinfunction "1_GND") (pintype "passive"))
      (node (ref "J5") (pin "GND2") (pinfunction "4_GND2") (pintype "passive"))
      (node (ref "J6") (pin "GND") (pinfunction "1_GND") (pintype "passive"))
      (node (ref "J6") (pin "GND2") (pinfunction "4_GND2") (pintype "passive"))
      (node (ref "J7") (pin "GND") (pinfunction "1_GND") (pintype "passive"))
      (node (ref "J7") (pin "GND2") (pinfunction "4_GND2") (pintype "passive"))
      (node (ref "J8") (pin "GND") (pinfunction "1_GND") (pintype "passive"))
      (node (ref "J8") (pin "GND2") (pinfunction "4_GND2") (pintype "passive"))
      (node (ref "J9") (pin "GND") (pinfunction "1_GND") (pintype "passive"))
      (node (ref "J9") (pin "GND2") (pinfunction "4_GND2") (pintype "passive"))
      (node (ref "JP1") (pin "1") (pinfunction "1_1") (pintype "passive"))
      (node (ref "JP2") (pin "2") (pinfunction "2_2") (pintype "passive"))
      (node (ref "LED2") (pin "K") (pinfunction "C_K") (pintype "passive"))
      (node (ref "LED3") (pin "K") (pinfunction "C_K") (pintype "passive"))
      (node (ref "LED4") (pin "K") (pinfunction "C_K") (pintype "passive"))
      (node (ref "Q2") (pin "E") (pinfunction "E_E") (pintype "passive"))
      (node (ref "Q3") (pin "E") (pinfunction "E_E") (pintype "passive"))
      (node (ref "R1") (pin "P$3") (pinfunction "A_P$3") (pintype "passive"))
      (node (ref "R10") (pin "1") (pinfunction "1_1") (pintype "passive"))
      (node (ref "R12") (pin "1") (pinfunction "1_1") (pintype "passive"))
      (node (ref "R2") (pin "P$3") (pinfunction "A_P$3") (pintype "passive"))
      (node (ref "R25") (pin "P$3") (pinfunction "A_P$3") (pintype "passive"))
      (node (ref "R26") (pin "P$3") (pinfunction "A_P$3") (pintype "passive"))
      (node (ref "R42") (pin "P$3") (pinfunction "A_P$3") (pintype "passive"))
      (node (ref "R46") (pin "P$3") (pinfunction "A_P$3") (pintype "passive"))
      (node (ref "R5") (pin "P$3") (pinfunction "A_P$3") (pintype "passive"))
      (node (ref "SW1") (pin "L2") (pinfunction "L2_L2") (pintype "passive"))
      (node (ref "SW1") (pin "P3") (pinfunction "A3_P3") (pintype "passive"))
      (node (ref "SW1") (pin "P6") (pinfunction "B3_P6") (pintype "passive"))
    )
    (net (code "25") (name "Net-(D1-PadA)") (class "Default")
      (node (ref "D1") (pin "A") (pinfunction "A_A") (pintype "passive"))
      (node (ref "J16") (pin "1") (pinfunction "1_1") (pintype "passive"))
    )
    (net (code "26") (name "Net-(IC1-AVCC)") (class "Default")
      (node (ref "C6") (pin "1") (pinfunction "1_1") (pintype "passive"))
      (node (ref "IC1") (pin "18") (pinfunction "AVCC_18") (pintype "bidirectional"))
      (node (ref "L1") (pin "2") (pinfunction "2_2") (pintype "passive"))
    )
    (net (code "27") (name "Net-(IC1-PB6(XTAL1{slash}TOSC1))") (class "Default")
      (node (ref "C2") (pin "2") (pinfunction "2_2") (pintype "passive"))
      (node (ref "IC1") (pin "7") (pinfunction "PB6(XTAL1/TOSC1)_7") (pintype "bidirectional"))
      (node (ref "Q1") (pin "2") (pinfunction "2_2") (pintype "passive"))
    )
    (net (code "28") (name "Net-(IC1-PB7(XTAL2{slash}TOSC2))") (class "Default")
      (node (ref "C7") (pin "2") (pinfunction "2_2") (pintype "passive"))
      (node (ref "IC1") (pin "8") (pinfunction "PB7(XTAL2/TOSC2)_8") (pintype "bidirectional"))
      (node (ref "Q1") (pin "1") (pinfunction "1_1") (pintype "passive"))
    )
    (net (code "29") (name "Net-(IC3A--IN)") (class "Default")
      (node (ref "C15") (pin "1") (pinfunction "1_1") (pintype "passive"))
      (node (ref "IC3") (pin "2") (pinfunction "-IN_2") (pintype "input"))
      (node (ref "R27") (pin "2") (pinfunction "2_2") (pintype "passive"))
      (node (ref "R30") (pin "1") (pinfunction "1_1") (pintype "passive"))
      (node (ref "R31") (pin "2") (pinfunction "2_2") (pintype "passive"))
      (node (ref "R32") (pin "2") (pinfunction "2_2") (pintype "passive"))
    )
    (net (code "30") (name "Net-(IC3B--IN)") (class "Default")
      (node (ref "C10") (pin "1") (pinfunction "1_1") (pintype "passive"))
      (node (ref "IC3") (pin "6") (pinfunction "-IN_6") (pintype "input"))
      (node (ref "R13") (pin "1") (pinfunction "1_1") (pintype "passive"))
      (node (ref "R14") (pin "2") (pinfunction "2_2") (pintype "passive"))
      (node (ref "R15") (pin "2") (pinfunction "2_2") (pintype "passive"))
      (node (ref "R22") (pin "2") (pinfunction "2_2") (pintype "passive"))
    )
    (net (code "31") (name "Net-(IC4A--IN)") (class "Default")
      (node (ref "C16") (pin "1") (pinfunction "1_1") (pintype "passive"))
      (node (ref "IC4") (pin "2") (pinfunction "-IN_2") (pintype "input"))
      (node (ref "R28") (pin "2") (pinfunction "2_2") (pintype "passive"))
      (node (ref "R33") (pin "1") (pinfunction "1_1") (pintype "passive"))
      (node (ref "R34") (pin "2") (pinfunction "2_2") (pintype "passive"))
      (node (ref "R35") (pin "2") (pinfunction "2_2") (pintype "passive"))
    )
    (net (code "32") (name "Net-(IC4B--IN)") (class "Default")
      (node (ref "C12") (pin "1") (pinfunction "1_1") (pintype "passive"))
      (node (ref "IC4") (pin "6") (pinfunction "-IN_6") (pintype "input"))
      (node (ref "R16") (pin "1") (pinfunction "1_1") (pintype "passive"))
      (node (ref "R17") (pin "2") (pinfunction "2_2") (pintype "passive"))
      (node (ref "R18") (pin "2") (pinfunction "2_2") (pintype "passive"))
      (node (ref "R23") (pin "2") (pinfunction "2_2") (pintype "passive"))
    )
    (net (code "33") (name "Net-(IC5A--IN)") (class "Default")
      (node (ref "C17") (pin "1") (pinfunction "1_1") (pintype "passive"))
      (node (ref "IC5") (pin "2") (pinfunction "-IN_2") (pintype "input"))
      (node (ref "R29") (pin "2") (pinfunction "2_2") (pintype "passive"))
      (node (ref "R36") (pin "1") (pinfunction "1_1") (pintype "passive"))
      (node (ref "R37") (pin "2") (pinfunction "2_2") (pintype "passive"))
      (node (ref "R38") (pin "2") (pinfunction "2_2") (pintype "passive"))
    )
    (net (code "34") (name "Net-(IC5B--IN)") (class "Default")
      (node (ref "C14") (pin "1") (pinfunction "1_1") (pintype "passive"))
      (node (ref "IC5") (pin "6") (pinfunction "-IN_6") (pintype "input"))
      (node (ref "R19") (pin "1") (pinfunction "1_1") (pintype "passive"))
      (node (ref "R20") (pin "2") (pinfunction "2_2") (pintype "passive"))
      (node (ref "R21") (pin "2") (pinfunction "2_2") (pintype "passive"))
      (node (ref "R24") (pin "2") (pinfunction "2_2") (pintype "passive"))
    )
    (net (code "35") (name "Net-(IC6A-QA)") (class "Default")
      (node (ref "IC6") (pin "15") (pinfunction "QA_15") (pintype "tri_state"))
      (node (ref "R45") (pin "1") (pinfunction "1_1") (pintype "passive"))
    )
    (net (code "36") (name "Net-(IC6A-QB)") (class "Default")
      (node (ref "IC6") (pin "1") (pinfunction "QB_1") (pintype "tri_state"))
      (node (ref "R44") (pin "1") (pinfunction "1_1") (pintype "passive"))
    )
    (net (code "37") (name "Net-(IC6A-QC)") (class "Default")
      (node (ref "IC6") (pin "2") (pinfunction "QC_2") (pintype "tri_state"))
      (node (ref "R43") (pin "1") (pinfunction "1_1") (pintype "passive"))
    )
    (net (code "38") (name "Net-(IC6A-QD)") (class "Default")
      (node (ref "IC6") (pin "3") (pinfunction "QD_3") (pintype "tri_state"))
      (node (ref "R49") (pin "1") (pinfunction "1_1") (pintype "passive"))
    )
    (net (code "39") (name "Net-(IC6A-QE)") (class "Default")
      (node (ref "IC6") (pin "4") (pinfunction "QE_4") (pintype "tri_state"))
      (node (ref "R48") (pin "1") (pinfunction "1_1") (pintype "passive"))
    )
    (net (code "40") (name "Net-(IC6A-QF)") (class "Default")
      (node (ref "IC6") (pin "5") (pinfunction "QF_5") (pintype "tri_state"))
      (node (ref "R47") (pin "1") (pinfunction "1_1") (pintype "passive"))
    )
    (net (code "41") (name "Net-(IC6A-QG)") (class "Default")
      (node (ref "IC6") (pin "6") (pinfunction "QG_6") (pintype "tri_state"))
      (node (ref "JP1") (pin "2") (pinfunction "2_2") (pintype "passive"))
    )
    (net (code "42") (name "Net-(IC6A-QH)") (class "Default")
      (node (ref "IC6") (pin "7") (pinfunction "QH_7") (pintype "tri_state"))
      (node (ref "JP1") (pin "3") (pinfunction "3_3") (pintype "passive"))
    )
    (net (code "43") (name "Net-(J1-2)") (class "Default")
      (node (ref "J1") (pin "TIP") (pinfunction "2_TIP") (pintype "passive"))
      (node (ref "R9") (pin "2") (pinfunction "2_2") (pintype "passive"))
    )
    (net (code "44") (name "Net-(J2-2)") (class "Default")
      (node (ref "J2") (pin "TIP") (pinfunction "2_TIP") (pintype "passive"))
      (node (ref "R11") (pin "2") (pinfunction "2_2") (pintype "passive"))
    )
    (net (code "45") (name "Net-(J3-2)") (class "Default")
      (node (ref "J3") (pin "TIP") (pinfunction "2_TIP") (pintype "passive"))
      (node (ref "R32") (pin "1") (pinfunction "1_1") (pintype "passive"))
    )
    (net (code "46") (name "Net-(J4-2)") (class "Default")
      (node (ref "J4") (pin "TIP") (pinfunction "2_TIP") (pintype "passive"))
      (node (ref "R15") (pin "1") (pinfunction "1_1") (pintype "passive"))
    )
    (net (code "47") (name "Net-(J5-2)") (class "Default")
      (node (ref "J5") (pin "TIP") (pinfunction "2_TIP") (pintype "passive"))
      (node (ref "R18") (pin "1") (pinfunction "1_1") (pintype "passive"))
    )
    (net (code "48") (name "Net-(J6-2)") (class "Default")
      (node (ref "J6") (pin "TIP") (pinfunction "2_TIP") (pintype "passive"))
      (node (ref "R37") (pin "1") (pinfunction "1_1") (pintype "passive"))
    )
    (net (code "49") (name "Net-(J7-2)") (class "Default")
      (node (ref "J7") (pin "TIP") (pinfunction "2_TIP") (pintype "passive"))
      (node (ref "R21") (pin "1") (pinfunction "1_1") (pintype "passive"))
    )
    (net (code "50") (name "Net-(J8-2)") (class "Default")
      (node (ref "J8") (pin "TIP") (pinfunction "2_TIP") (pintype "passive"))
      (node (ref "R45") (pin "2") (pinfunction "2_2") (pintype "passive"))
    )
    (net (code "51") (name "Net-(J9-2)") (class "Default")
      (node (ref "J9") (pin "TIP") (pinfunction "2_TIP") (pintype "passive"))
      (node (ref "R44") (pin "2") (pinfunction "2_2") (pintype "passive"))
    )
    (net (code "52") (name "Net-(J10-2)") (class "Default")
      (node (ref "J10") (pin "TIP") (pinfunction "2_TIP") (pintype "passive"))
      (node (ref "R43") (pin "2") (pinfunction "2_2") (pintype "passive"))
    )
    (net (code "53") (name "Net-(J11-2)") (class "Default")
      (node (ref "J11") (pin "TIP") (pinfunction "2_TIP") (pintype "passive"))
      (node (ref "R34") (pin "1") (pinfunction "1_1") (pintype "passive"))
    )
    (net (code "54") (name "Net-(J12-2)") (class "Default")
      (node (ref "J12") (pin "TIP") (pinfunction "2_TIP") (pintype "passive"))
      (node (ref "R49") (pin "2") (pinfunction "2_2") (pintype "passive"))
    )
    (net (code "55") (name "Net-(J13-2)") (class "Default")
      (node (ref "J13") (pin "TIP") (pinfunction "2_TIP") (pintype "passive"))
      (node (ref "R48") (pin "2") (pinfunction "2_2") (pintype "passive"))
    )
    (net (code "56") (name "Net-(J14-2)") (class "Default")
      (node (ref "J14") (pin "TIP") (pinfunction "2_TIP") (pintype "passive"))
      (node (ref "R47") (pin "2") (pinfunction "2_2") (pintype "passive"))
    )
    (net (code "57") (name "Net-(LED2-PadA)") (class "Default")
      (node (ref "LED2") (pin "A") (pinfunction "A_A") (pintype "passive"))
      (node (ref "R39") (pin "2") (pinfunction "2_2") (pintype "passive"))
    )
    (net (code "58") (name "Net-(LED3-PadA)") (class "Default")
      (node (ref "LED3") (pin "A") (pinfunction "A_A") (pintype "passive"))
      (node (ref "R40") (pin "2") (pinfunction "2_2") (pintype "passive"))
    )
    (net (code "59") (name "Net-(LED4-PadA)") (class "Default")
      (node (ref "LED4") (pin "A") (pinfunction "A_A") (pintype "passive"))
      (node (ref "R41") (pin "2") (pinfunction "2_2") (pintype "passive"))
    )
    (net (code "60") (name "Net-(Q2-PadB)") (class "Default")
      (node (ref "Q2") (pin "B") (pinfunction "B_B") (pintype "passive"))
      (node (ref "R10") (pin "2") (pinfunction "2_2") (pintype "passive"))
      (node (ref "R9") (pin "1") (pinfunction "1_1") (pintype "passive"))
    )
    (net (code "61") (name "Net-(Q3-PadB)") (class "Default")
      (node (ref "Q3") (pin "B") (pinfunction "B_B") (pintype "passive"))
      (node (ref "R11") (pin "1") (pinfunction "1_1") (pintype "passive"))
      (node (ref "R12") (pin "2") (pinfunction "2_2") (pintype "passive"))
    )
    (net (code "62") (name "Net-(R2-S)") (class "Default")
      (node (ref "R17") (pin "1") (pinfunction "1_1") (pintype "passive"))
      (node (ref "R2") (pin "P$2") (pinfunction "S_P$2") (pintype "passive"))
    )
    (net (code "63") (name "Net-(R4-Pad2)") (class "Default")
      (node (ref "R4") (pin "2") (pinfunction "2_2") (pintype "passive"))
      (node (ref "SW1") (pin "L1") (pinfunction "L1_L1") (pintype "passive"))
    )
    (net (code "64") (name "Net-(R5-S)") (class "Default")
      (node (ref "R38") (pin "1") (pinfunction "1_1") (pintype "passive"))
      (node (ref "R5") (pin "P$2") (pinfunction "S_P$2") (pintype "passive"))
    )
    (net (code "65") (name "Net-(R25-S)") (class "Default")
      (node (ref "R25") (pin "P$2") (pinfunction "S_P$2") (pintype "passive"))
      (node (ref "R31") (pin "1") (pinfunction "1_1") (pintype "passive"))
    )
    (net (code "66") (name "Net-(R26-S)") (class "Default")
      (node (ref "R20") (pin "1") (pinfunction "1_1") (pintype "passive"))
      (node (ref "R26") (pin "P$2") (pinfunction "S_P$2") (pintype "passive"))
    )
    (net (code "67") (name "Net-(R42-S)") (class "Default")
      (node (ref "R14") (pin "1") (pinfunction "1_1") (pintype "passive"))
      (node (ref "R42") (pin "P$2") (pinfunction "S_P$2") (pintype "passive"))
    )
    (net (code "68") (name "Net-(R46-S)") (class "Default")
      (node (ref "R35") (pin "1") (pinfunction "1_1") (pintype "passive"))
      (node (ref "R46") (pin "P$2") (pinfunction "S_P$2") (pintype "passive"))
    )
    (net (code "69") (name "VCC") (class "Default")
      (node (ref "C19") (pin "+") (pinfunction "+_+") (pintype "passive"))
      (node (ref "D1") (pin "C") (pinfunction "C_C") (pintype "passive"))
      (node (ref "IC7") (pin "3") (pinfunction "VIN_3") (pintype "input"))
    )
    (net (code "70") (name "VEE") (class "Default")
      (node (ref "J16") (pin "10") (pinfunction "10_10") (pintype "passive"))
      (node (ref "J16") (pin "9") (pinfunction "9_9") (pintype "passive"))
      (node (ref "R8") (pin "1") (pinfunction "1_1") (pintype "passive"))
    )
    (net (code "71") (name "unconnected-(IC1-ADC7-Pad22)") (class "Default")
      (node (ref "IC1") (pin "22") (pinfunction "ADC7_22") (pintype "bidirectional"))
    )
    (net (code "72") (name "unconnected-(IC1-PB0(ICP)-Pad12)") (class "Default")
      (node (ref "IC1") (pin "12") (pinfunction "PB0(ICP)_12") (pintype "bidirectional"))
    )
    (net (code "73") (name "unconnected-(IC1-PB1(OC1A)-Pad13)") (class "Default")
      (node (ref "IC1") (pin "13") (pinfunction "PB1(OC1A)_13") (pintype "bidirectional"))
    )
    (net (code "74") (name "unconnected-(IC6A-QH*-Pad9)") (class "Default")
      (node (ref "IC6") (pin "9") (pinfunction "QH*_9") (pintype "tri_state"))
    )
    (net (code "75") (name "unconnected-(J1-3-PadSW)") (class "Default")
      (node (ref "J1") (pin "SW") (pinfunction "3_SW") (pintype "passive"))
    )
    (net (code "76") (name "unconnected-(J2-3-PadSW)") (class "Default")
      (node (ref "J2") (pin "SW") (pinfunction "3_SW") (pintype "passive"))
    )
    (net (code "77") (name "unconnected-(J3-3-PadSW)") (class "Default")
      (node (ref "J3") (pin "SW") (pinfunction "3_SW") (pintype "passive"))
    )
    (net (code "78") (name "unconnected-(J4-3-PadSW)") (class "Default")
      (node (ref "J4") (pin "SW") (pinfunction "3_SW") (pintype "passive"))
    )
    (net (code "79") (name "unconnected-(J5-3-PadSW)") (class "Default")
      (node (ref "J5") (pin "SW") (pinfunction "3_SW") (pintype "passive"))
    )
    (net (code "80") (name "unconnected-(J6-3-PadSW)") (class "Default")
      (node (ref "J6") (pin "SW") (pinfunction "3_SW") (pintype "passive"))
    )
    (net (code "81") (name "unconnected-(J7-3-PadSW)") (class "Default")
      (node (ref "J7") (pin "SW") (pinfunction "3_SW") (pintype "passive"))
    )
    (net (code "82") (name "unconnected-(J8-3-PadSW)") (class "Default")
      (node (ref "J8") (pin "SW") (pinfunction "3_SW") (pintype "passive"))
    )
    (net (code "83") (name "unconnected-(J9-3-PadSW)") (class "Default")
      (node (ref "J9") (pin "SW") (pinfunction "3_SW") (pintype "passive"))
    )
    (net (code "84") (name "unconnected-(J10-3-PadSW)") (class "Default")
      (node (ref "J10") (pin "SW") (pinfunction "3_SW") (pintype "passive"))
    )
    (net (code "85") (name "unconnected-(J11-3-PadSW)") (class "Default")
      (node (ref "J11") (pin "SW") (pinfunction "3_SW") (pintype "passive"))
    )
    (net (code "86") (name "unconnected-(J12-3-PadSW)") (class "Default")
      (node (ref "J12") (pin "SW") (pinfunction "3_SW") (pintype "passive"))
    )
    (net (code "87") (name "unconnected-(J13-3-PadSW)") (class "Default")
      (node (ref "J13") (pin "SW") (pinfunction "3_SW") (pintype "passive"))
    )
    (net (code "88") (name "unconnected-(J14-3-PadSW)") (class "Default")
      (node (ref "J14") (pin "SW") (pinfunction "3_SW") (pintype "passive"))
    )
    (net (code "89") (name "unconnected-(J16-Pad2)") (class "Default")
      (node (ref "J16") (pin "2") (pinfunction "2_2") (pintype "passive"))
    )
    (net (code "90") (name "unconnected-(SW1A-A1-PadP1)") (class "Default")
      (node (ref "SW1") (pin "P1") (pinfunction "A1_P1") (pintype "passive"))
    )
    (net (code "91") (name "unconnected-(SW1A-B1-PadP4)") (class "Default")
      (node (ref "SW1") (pin "P4") (pinfunction "B1_P4") (pintype "passive"))
    )
  )
)
